# Flash.net
KiCad netlist of a schematic drawn in Altium Designer
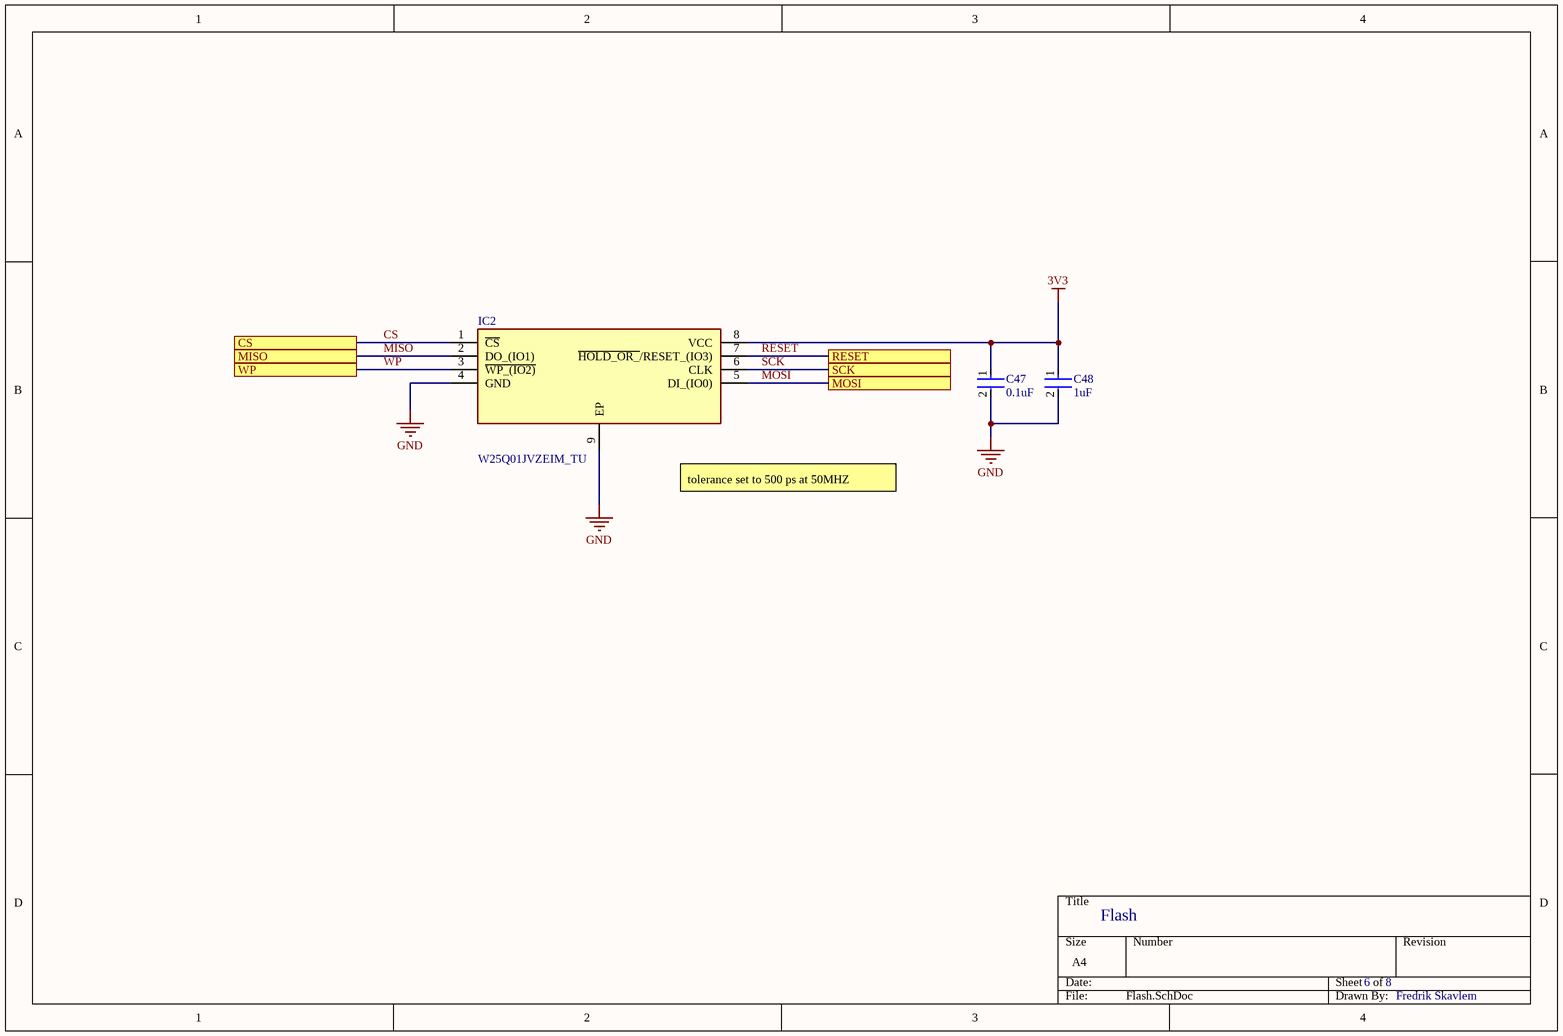
[diagram p0: Flash.SchDoc]

(export (version "E")
  (design (tool "Eeschema 10.0.6"))
  (components
    (comp (ref "C47")
      (value "0.1uF")
      (footprint "FP-CL10-IPC_C")
      (description "Cap Ceramic 100nF 16V X7R ±10% Pad SMD 0603 +125°C T/R\r\nCL10B104KO8WPNC")
      (fields (field (name "TOLERANCE") "10%"))
      (libsource (lib "Altium Content Vault") (part "b4654b650e69147ec39a6b967a45e02"))
    )
    (comp (ref "C48")
      (value "1uF")
      (footprint "FP-CL10-IPC_C")
      (description "Cap Ceramic 1uF 16V X7R ±10% Pad SMD 0603 +125°C T/R\r\nCL10B105KO8NNNL")
      (fields (field (name "TOLERANCE") "10%"))
      (libsource (lib "Altium Content Vault") (part "b4654b650e69147ec39a6b967a45e02"))
    )
    (comp (ref "IC2")
      (value "W25Q01JVZEIM_TU")
      (footprint "SamacSys:SON127P800X600X80-9N-D")
      (description "Integrated Circuit")
      (fields
        (field (name "MANUFACTURER_PART_NUMBER") "W25Q01JVZEIM TU")
        (field (name "MOUSER PART NUMBER") "454-W25Q01JVZEIMTU")
      )
      (libsource (lib "*") (part "W25Q01JVZEIM_TU"))
    )
  )
  (nets
    (net (code "1") (name "/CS") (class "Default")
      (node (ref "IC2") (pin "1") (pinfunction "~{CS}_1") (pintype "passive"))
    )
    (net (code "2") (name "/MISO") (class "Default")
      (node (ref "IC2") (pin "2") (pinfunction "DO_(IO1)_2") (pintype "passive"))
    )
    (net (code "3") (name "/MOSI") (class "Default")
      (node (ref "IC2") (pin "5") (pinfunction "DI_(IO0)_5") (pintype "passive"))
    )
    (net (code "4") (name "/RESET") (class "Default")
      (node (ref "IC2") (pin "7") (pinfunction "~{HOLD_OR_}/RESET_(IO3)_7") (pintype "passive"))
    )
    (net (code "5") (name "/SCK") (class "Default")
      (node (ref "IC2") (pin "6") (pinfunction "CLK_6") (pintype "passive"))
    )
    (net (code "6") (name "/WP") (class "Default")
      (node (ref "IC2") (pin "3") (pinfunction "~{WP_(IO2)}_3") (pintype "passive"))
    )
    (net (code "7") (name "3V3") (class "Default")
      (node (ref "C47") (pin "1") (pinfunction "1_1") (pintype "passive"))
      (node (ref "C48") (pin "1") (pinfunction "1_1") (pintype "passive"))
      (node (ref "IC2") (pin "8") (pinfunction "VCC_8") (pintype "passive"))
    )
    (net (code "8") (name "GND") (class "Default")
      (node (ref "C47") (pin "2") (pinfunction "2_2") (pintype "passive"))
      (node (ref "C48") (pin "2") (pinfunction "2_2") (pintype "passive"))
      (node (ref "IC2") (pin "4") (pinfunction "GND_4") (pintype "passive"))
      (node (ref "IC2") (pin "9") (pinfunction "EP_9") (pintype "passive"))
    )
  )
)
